# SCH_Mobile-robot.net
KiCad netlist of a schematic drawn in Altium Designer
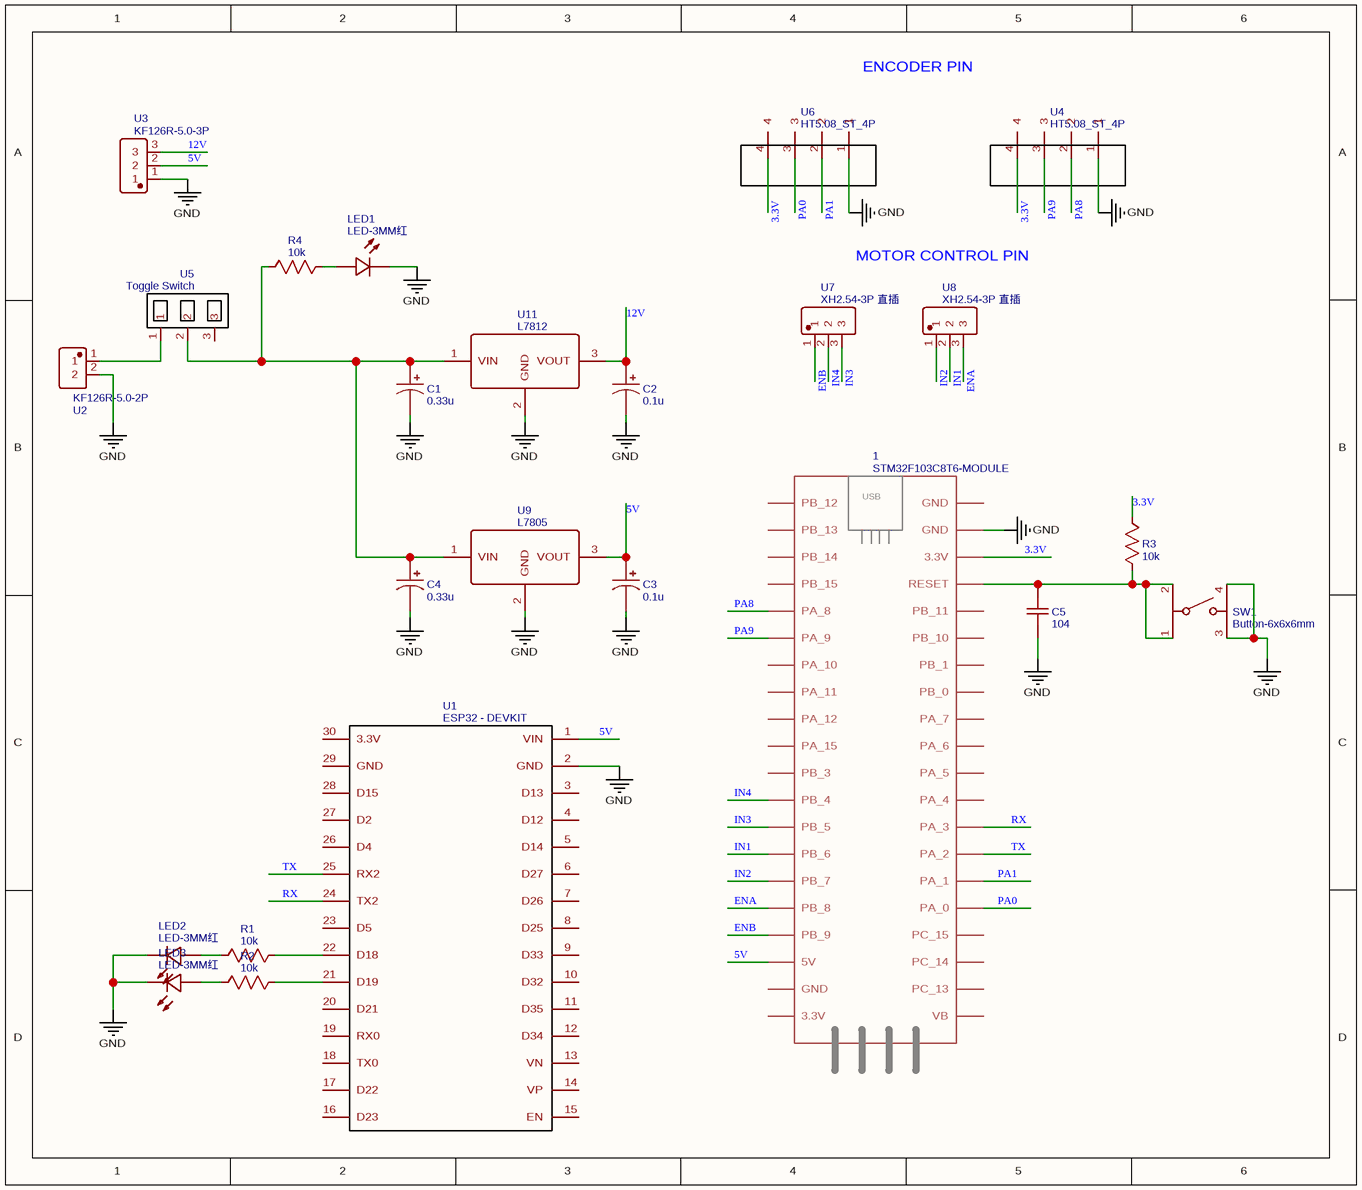
[diagram p0: SCH_Mobile-robot.schdoc]

(export (version "E")
  (design (tool "Eeschema 10.0.6"))
  (components
    (comp (ref "1")
      (value "STM32F103C8T6-MODULE")
      (fields (field (name "CONTRIBUTOR") "minhnhathust2002"))
      (libsource (lib "altium-import") (part "root_3_STM32F103C8T6-MODULE_"))
    )
    (comp (ref "C1")
      (value "0.33u")
      (fields (field (name "CONTRIBUTOR") "LCEDA_Lib"))
      (libsource (lib "altium-import") (part "root_3_0.33u_"))
    )
    (comp (ref "C2")
      (value "0.1u")
      (fields (field (name "CONTRIBUTOR") "LCEDA_Lib"))
      (libsource (lib "altium-import") (part "root_3_0.1u_"))
    )
    (comp (ref "C3")
      (value "0.1u")
      (fields (field (name "CONTRIBUTOR") "LCEDA_Lib"))
      (libsource (lib "altium-import") (part "root_3_0.1u_"))
    )
    (comp (ref "C4")
      (value "0.33u")
      (fields (field (name "CONTRIBUTOR") "LCEDA_Lib"))
      (libsource (lib "altium-import") (part "root_3_0.33u_"))
    )
    (comp (ref "C5")
      (value "104")
      (fields (field (name "CONTRIBUTOR") "LCEDA_Lib"))
      (libsource (lib "altium-import") (part "root_1_104_"))
    )
    (comp (ref "LED1")
      (value "LED-3MM红")
      (fields (field (name "MANUFACTURER PART") "LED-3mm红") (field (name "CONTRIBUTOR") "LCSC"))
      (libsource (lib "altium-import") (part "root_0_LED-3MM红_"))
    )
    (comp (ref "LED2")
      (value "LED-3MM红")
      (fields (field (name "MANUFACTURER PART") "LED-3mm红") (field (name "CONTRIBUTOR") "LCSC"))
      (libsource (lib "altium-import") (part "root_2_LED-3MM红_"))
    )
    (comp (ref "LED3")
      (value "LED-3MM红")
      (fields (field (name "MANUFACTURER PART") "LED-3mm红") (field (name "CONTRIBUTOR") "LCSC"))
      (libsource (lib "altium-import") (part "root_2_LED-3MM红_"))
    )
    (comp (ref "R1")
      (value "10k")
      (fields (field (name "CONTRIBUTOR") "LCEDA_Lib"))
      (libsource (lib "altium-import") (part "root_2_10k_"))
    )
    (comp (ref "R2")
      (value "10k")
      (fields (field (name "CONTRIBUTOR") "LCEDA_Lib"))
      (libsource (lib "altium-import") (part "root_2_10k_"))
    )
    (comp (ref "R3")
      (value "10k")
      (fields (field (name "CONTRIBUTOR") "LCEDA_Lib"))
      (libsource (lib "altium-import") (part "root_3_10k_"))
    )
    (comp (ref "R4")
      (value "10k")
      (fields (field (name "CONTRIBUTOR") "LCEDA_Lib"))
      (libsource (lib "altium-import") (part "root_2_10k_"))
    )
    (comp (ref "SW1")
      (value "Button-6x6x6mm")
      (fields
        (field (name "MANUFACTURER") "BBJ")
        (field (name "MANUFACTURER PART") "Switch,6*6*6Plastic head,260G, 0.25mm,Straight line")
      )
      (libsource (lib "altium-import") (part "root_1_Button-6x6x6mm_"))
    )
    (comp (ref "U1")
      (value "ESP32 - DEVKIT")
      (fields (field (name "CONTRIBUTOR") "minhnhathust2002"))
      (libsource (lib "altium-import") (part "root_0_ESP32 - DEVKIT_"))
    )
    (comp (ref "U2")
      (value "KF126R-5.0-2P")
      (fields (field (name "MANUFACTURER") "KEFA(科发)") (field (name "CONTRIBUTOR") "LCSC"))
      (libsource (lib "altium-import") (part "root_2_KF126R-5.0-2P_"))
    )
    (comp (ref "U3")
      (value "KF126R-5.0-3P")
      (fields (field (name "MANUFACTURER") "KEFA(科发)") (field (name "CONTRIBUTOR") "LCSC"))
      (libsource (lib "altium-import") (part "root_2_KF126R-5.0-3P_"))
    )
    (comp (ref "U4")
      (value "HT5.08_ST_4P")
      (fields (field (name "CONTRIBUTOR") "thomas720"))
      (libsource (lib "altium-import") (part "root_3_HT5.08_ST_4P_"))
    )
    (comp (ref "U5")
      (value "Toggle Switch")
      (fields (field (name "CONTRIBUTOR") "minhnhathust2002"))
      (libsource (lib "altium-import") (part "root_2_Toggle Switch_"))
    )
    (comp (ref "U6")
      (value "HT5.08_ST_4P")
      (fields (field (name "CONTRIBUTOR") "thomas720"))
      (libsource (lib "altium-import") (part "root_3_HT5.08_ST_4P_"))
    )
    (comp (ref "U7")
      (value "XH2.54-3P 直插")
      (fields (field (name "CONTRIBUTOR") "LCSC"))
      (libsource (lib "altium-import") (part "root_1_XH2.54-3P 直插_"))
    )
    (comp (ref "U8")
      (value "XH2.54-3P 直插")
      (fields (field (name "CONTRIBUTOR") "LCSC"))
      (libsource (lib "altium-import") (part "root_1_XH2.54-3P 直插_"))
    )
    (comp (ref "U9")
      (value "L7805")
      (fields
        (field (name "MANUFACTURER") "FeiHong(飞虹)")
        (field (name "MANUFACTURER PART") "KA7812B")
        (field (name "CONTRIBUTOR") "LCSC")
      )
      (libsource (lib "altium-import") (part "root_0_L7805_"))
    )
    (comp (ref "U11")
      (value "L7812")
      (fields
        (field (name "MANUFACTURER") "FeiHong(飞虹)")
        (field (name "MANUFACTURER PART") "KA7812B")
        (field (name "CONTRIBUTOR") "LCSC")
      )
      (libsource (lib "altium-import") (part "root_0_L7812_"))
    )
  )
  (nets
    (net (code "1") (name "/3.3V") (class "Default")
      (node (ref "1") (pin "3.3V_2") (pinfunction "3.3V_3.3V_2") (pintype "passive"))
      (node (ref "R3") (pin "1") (pinfunction "1_1") (pintype "passive"))
      (node (ref "U4") (pin "4") (pinfunction "4_4") (pintype "passive"))
      (node (ref "U6") (pin "4") (pinfunction "4_4") (pintype "passive"))
    )
    (net (code "2") (name "/5V") (class "Default")
      (node (ref "1") (pin "5V") (pinfunction "5V_5V") (pintype "passive"))
      (node (ref "C3") (pin "1") (pinfunction "1_1") (pintype "passive"))
      (node (ref "U1") (pin "1") (pinfunction "VIN_1") (pintype "passive"))
      (node (ref "U3") (pin "2") (pinfunction "2_2") (pintype "passive"))
      (node (ref "U9") (pin "3") (pinfunction "VOUT_3") (pintype "passive"))
    )
    (net (code "3") (name "/12V") (class "Default")
      (node (ref "C2") (pin "1") (pinfunction "1_1") (pintype "passive"))
      (node (ref "U11") (pin "3") (pinfunction "VOUT_3") (pintype "passive"))
      (node (ref "U3") (pin "3") (pinfunction "3_3") (pintype "passive"))
    )
    (net (code "4") (name "/ENA") (class "Default")
      (node (ref "1") (pin "PB_8") (pinfunction "PB_8_PB_8") (pintype "passive"))
      (node (ref "U8") (pin "3") (pinfunction "3_3") (pintype "passive"))
    )
    (net (code "5") (name "/ENB") (class "Default")
      (node (ref "1") (pin "PB_9") (pinfunction "PB_9_PB_9") (pintype "passive"))
      (node (ref "U7") (pin "1") (pinfunction "1_1") (pintype "passive"))
    )
    (net (code "6") (name "/IN1") (class "Default")
      (node (ref "1") (pin "PB_6") (pinfunction "PB_6_PB_6") (pintype "passive"))
      (node (ref "U8") (pin "2") (pinfunction "2_2") (pintype "passive"))
    )
    (net (code "7") (name "/IN2") (class "Default")
      (node (ref "1") (pin "PB_7") (pinfunction "PB_7_PB_7") (pintype "passive"))
      (node (ref "U8") (pin "1") (pinfunction "1_1") (pintype "passive"))
    )
    (net (code "8") (name "/IN3") (class "Default")
      (node (ref "1") (pin "PB_5") (pinfunction "PB_5_PB_5") (pintype "passive"))
      (node (ref "U7") (pin "3") (pinfunction "3_3") (pintype "passive"))
    )
    (net (code "9") (name "/IN4") (class "Default")
      (node (ref "1") (pin "PB_4") (pinfunction "PB_4_PB_4") (pintype "passive"))
      (node (ref "U7") (pin "2") (pinfunction "2_2") (pintype "passive"))
    )
    (net (code "10") (name "/PA0") (class "Default")
      (node (ref "1") (pin "PA_0") (pinfunction "PA_0_PA_0") (pintype "passive"))
      (node (ref "U6") (pin "3") (pinfunction "3_3") (pintype "passive"))
    )
    (net (code "11") (name "/PA1") (class "Default")
      (node (ref "1") (pin "PA_1") (pinfunction "PA_1_PA_1") (pintype "passive"))
      (node (ref "U6") (pin "2") (pinfunction "2_2") (pintype "passive"))
    )
    (net (code "12") (name "/PA8") (class "Default")
      (node (ref "1") (pin "PA_8") (pinfunction "PA_8_PA_8") (pintype "passive"))
      (node (ref "U4") (pin "2") (pinfunction "2_2") (pintype "passive"))
    )
    (net (code "13") (name "/PA9") (class "Default")
      (node (ref "1") (pin "PA_9") (pinfunction "PA_9_PA_9") (pintype "passive"))
      (node (ref "U4") (pin "3") (pinfunction "3_3") (pintype "passive"))
    )
    (net (code "14") (name "/RX") (class "Default")
      (node (ref "1") (pin "PA_3") (pinfunction "PA_3_PA_3") (pintype "passive"))
      (node (ref "U1") (pin "24") (pinfunction "TX2_24") (pintype "passive"))
    )
    (net (code "15") (name "/TX") (class "Default")
      (node (ref "1") (pin "PA_2") (pinfunction "PA_2_PA_2") (pintype "passive"))
      (node (ref "U1") (pin "25") (pinfunction "RX2_25") (pintype "passive"))
    )
    (net (code "16") (name "GND") (class "Default")
      (node (ref "1") (pin "GND_2") (pinfunction "GND_GND_2") (pintype "passive"))
      (node (ref "C1") (pin "2") (pinfunction "2_2") (pintype "passive"))
      (node (ref "C2") (pin "2") (pinfunction "2_2") (pintype "passive"))
      (node (ref "C3") (pin "2") (pinfunction "2_2") (pintype "passive"))
      (node (ref "C4") (pin "2") (pinfunction "2_2") (pintype "passive"))
      (node (ref "C5") (pin "1") (pinfunction "1_1") (pintype "passive"))
      (node (ref "LED1") (pin "2") (pinfunction "2_2") (pintype "passive"))
      (node (ref "LED2") (pin "2") (pinfunction "2_2") (pintype "passive"))
      (node (ref "LED3") (pin "2") (pinfunction "2_2") (pintype "passive"))
      (node (ref "SW1") (pin "3") (pinfunction "3_3") (pintype "passive"))
      (node (ref "SW1") (pin "4") (pinfunction "4_4") (pintype "passive"))
      (node (ref "U1") (pin "2") (pinfunction "GND_2") (pintype "passive"))
      (node (ref "U11") (pin "2") (pinfunction "GND_2") (pintype "passive"))
      (node (ref "U2") (pin "2") (pinfunction "2_2") (pintype "passive"))
      (node (ref "U3") (pin "1") (pinfunction "1_1") (pintype "passive"))
      (node (ref "U4") (pin "1") (pinfunction "1_1") (pintype "passive"))
      (node (ref "U6") (pin "1") (pinfunction "1_1") (pintype "passive"))
      (node (ref "U9") (pin "2") (pinfunction "GND_2") (pintype "passive"))
    )
    (net (code "17") (name "Net-(1-PadRESET)") (class "Default")
      (node (ref "1") (pin "RESET") (pinfunction "RESET_RESET") (pintype "passive"))
      (node (ref "C5") (pin "2") (pinfunction "2_2") (pintype "passive"))
      (node (ref "R3") (pin "2") (pinfunction "2_2") (pintype "passive"))
      (node (ref "SW1") (pin "1") (pinfunction "1_1") (pintype "passive"))
      (node (ref "SW1") (pin "2") (pinfunction "2_2") (pintype "passive"))
    )
    (net (code "18") (name "Net-(LED1-Pad1)") (class "Default")
      (node (ref "LED1") (pin "1") (pinfunction "1_1") (pintype "passive"))
      (node (ref "R4") (pin "1") (pinfunction "1_1") (pintype "passive"))
    )
    (net (code "19") (name "Net-(LED2-Pad1)") (class "Default")
      (node (ref "LED2") (pin "1") (pinfunction "1_1") (pintype "passive"))
      (node (ref "R1") (pin "2") (pinfunction "2_2") (pintype "passive"))
    )
    (net (code "20") (name "Net-(LED3-Pad1)") (class "Default")
      (node (ref "LED3") (pin "1") (pinfunction "1_1") (pintype "passive"))
      (node (ref "R2") (pin "2") (pinfunction "2_2") (pintype "passive"))
    )
    (net (code "21") (name "Net-(U1-D18)") (class "Default")
      (node (ref "R1") (pin "1") (pinfunction "1_1") (pintype "passive"))
      (node (ref "U1") (pin "22") (pinfunction "D18_22") (pintype "passive"))
    )
    (net (code "22") (name "Net-(U1-D19)") (class "Default")
      (node (ref "R2") (pin "1") (pinfunction "1_1") (pintype "passive"))
      (node (ref "U1") (pin "21") (pinfunction "D19_21") (pintype "passive"))
    )
    (net (code "23") (name "Net-(U2-Pad1)") (class "Default")
      (node (ref "U2") (pin "1") (pinfunction "1_1") (pintype "passive"))
      (node (ref "U5") (pin "1") (pinfunction "1_1") (pintype "passive"))
    )
    (net (code "24") (name "Net-(U11-VIN)") (class "Default")
      (node (ref "C1") (pin "1") (pinfunction "1_1") (pintype "passive"))
      (node (ref "C4") (pin "1") (pinfunction "1_1") (pintype "passive"))
      (node (ref "R4") (pin "2") (pinfunction "2_2") (pintype "passive"))
      (node (ref "U11") (pin "1") (pinfunction "VIN_1") (pintype "passive"))
      (node (ref "U5") (pin "2") (pinfunction "2_2") (pintype "passive"))
      (node (ref "U9") (pin "1") (pinfunction "VIN_1") (pintype "passive"))
    )
    (net (code "25") (name "unconnected-(1-3.3V-Pad3.3V_1)") (class "Default")
      (node (ref "1") (pin "3.3V_1") (pinfunction "3.3V_3.3V_1") (pintype "passive"))
    )
    (net (code "26") (name "unconnected-(1-GND-PadGND_1)") (class "Default")
      (node (ref "1") (pin "GND_1") (pinfunction "GND_GND_1") (pintype "passive"))
    )
    (net (code "27") (name "unconnected-(1-GND-PadGND_3)") (class "Default")
      (node (ref "1") (pin "GND_3") (pinfunction "GND_GND_3") (pintype "passive"))
    )
    (net (code "28") (name "unconnected-(1-PadPA_4)") (class "Default")
      (node (ref "1") (pin "PA_4") (pinfunction "PA_4_PA_4") (pintype "passive"))
    )
    (net (code "29") (name "unconnected-(1-PadPA_5)") (class "Default")
      (node (ref "1") (pin "PA_5") (pinfunction "PA_5_PA_5") (pintype "passive"))
    )
    (net (code "30") (name "unconnected-(1-PadPA_6)") (class "Default")
      (node (ref "1") (pin "PA_6") (pinfunction "PA_6_PA_6") (pintype "passive"))
    )
    (net (code "31") (name "unconnected-(1-PadPA_7)") (class "Default")
      (node (ref "1") (pin "PA_7") (pinfunction "PA_7_PA_7") (pintype "passive"))
    )
    (net (code "32") (name "unconnected-(1-PadPA_10)") (class "Default")
      (node (ref "1") (pin "PA_10") (pinfunction "PA_10_PA_10") (pintype "passive"))
    )
    (net (code "33") (name "unconnected-(1-PadPA_11)") (class "Default")
      (node (ref "1") (pin "PA_11") (pinfunction "PA_11_PA_11") (pintype "passive"))
    )
    (net (code "34") (name "unconnected-(1-PadPA_12)") (class "Default")
      (node (ref "1") (pin "PA_12") (pinfunction "PA_12_PA_12") (pintype "passive"))
    )
    (net (code "35") (name "unconnected-(1-PadPA_15)") (class "Default")
      (node (ref "1") (pin "PA_15") (pinfunction "PA_15_PA_15") (pintype "passive"))
    )
    (net (code "36") (name "unconnected-(1-PadPB_0)") (class "Default")
      (node (ref "1") (pin "PB_0") (pinfunction "PB_0_PB_0") (pintype "passive"))
    )
    (net (code "37") (name "unconnected-(1-PadPB_1)") (class "Default")
      (node (ref "1") (pin "PB_1") (pinfunction "PB_1_PB_1") (pintype "passive"))
    )
    (net (code "38") (name "unconnected-(1-PadPB_3)") (class "Default")
      (node (ref "1") (pin "PB_3") (pinfunction "PB_3_PB_3") (pintype "passive"))
    )
    (net (code "39") (name "unconnected-(1-PadPB_10)") (class "Default")
      (node (ref "1") (pin "PB_10") (pinfunction "PB_10_PB_10") (pintype "passive"))
    )
    (net (code "40") (name "unconnected-(1-PadPB_11)") (class "Default")
      (node (ref "1") (pin "PB_11") (pinfunction "PB_11_PB_11") (pintype "passive"))
    )
    (net (code "41") (name "unconnected-(1-PadPB_12)") (class "Default")
      (node (ref "1") (pin "PB_12") (pinfunction "PB_12_PB_12") (pintype "passive"))
    )
    (net (code "42") (name "unconnected-(1-PadPB_13)") (class "Default")
      (node (ref "1") (pin "PB_13") (pinfunction "PB_13_PB_13") (pintype "passive"))
    )
    (net (code "43") (name "unconnected-(1-PadPB_14)") (class "Default")
      (node (ref "1") (pin "PB_14") (pinfunction "PB_14_PB_14") (pintype "passive"))
    )
    (net (code "44") (name "unconnected-(1-PadPB_15)") (class "Default")
      (node (ref "1") (pin "PB_15") (pinfunction "PB_15_PB_15") (pintype "passive"))
    )
    (net (code "45") (name "unconnected-(1-PadPC_13)") (class "Default")
      (node (ref "1") (pin "PC_13") (pinfunction "PC_13_PC_13") (pintype "passive"))
    )
    (net (code "46") (name "unconnected-(1-PadPC_14)") (class "Default")
      (node (ref "1") (pin "PC_14") (pinfunction "PC_14_PC_14") (pintype "passive"))
    )
    (net (code "47") (name "unconnected-(1-PadPC_15)") (class "Default")
      (node (ref "1") (pin "PC_15") (pinfunction "PC_15_PC_15") (pintype "passive"))
    )
    (net (code "48") (name "unconnected-(1-PadVB)") (class "Default")
      (node (ref "1") (pin "VB") (pinfunction "VB_VB") (pintype "passive"))
    )
    (net (code "49") (name "unconnected-(U1-3.3V-Pad30)") (class "Default")
      (node (ref "U1") (pin "30") (pinfunction "3.3V_30") (pintype "passive"))
    )
    (net (code "50") (name "unconnected-(U1-D2-Pad27)") (class "Default")
      (node (ref "U1") (pin "27") (pinfunction "D2_27") (pintype "passive"))
    )
    (net (code "51") (name "unconnected-(U1-D4-Pad26)") (class "Default")
      (node (ref "U1") (pin "26") (pinfunction "D4_26") (pintype "passive"))
    )
    (net (code "52") (name "unconnected-(U1-D5-Pad23)") (class "Default")
      (node (ref "U1") (pin "23") (pinfunction "D5_23") (pintype "passive"))
    )
    (net (code "53") (name "unconnected-(U1-D12-Pad4)") (class "Default")
      (node (ref "U1") (pin "4") (pinfunction "D12_4") (pintype "passive"))
    )
    (net (code "54") (name "unconnected-(U1-D13-Pad3)") (class "Default")
      (node (ref "U1") (pin "3") (pinfunction "D13_3") (pintype "passive"))
    )
    (net (code "55") (name "unconnected-(U1-D14-Pad5)") (class "Default")
      (node (ref "U1") (pin "5") (pinfunction "D14_5") (pintype "passive"))
    )
    (net (code "56") (name "unconnected-(U1-D15-Pad28)") (class "Default")
      (node (ref "U1") (pin "28") (pinfunction "D15_28") (pintype "passive"))
    )
    (net (code "57") (name "unconnected-(U1-D21-Pad20)") (class "Default")
      (node (ref "U1") (pin "20") (pinfunction "D21_20") (pintype "passive"))
    )
    (net (code "58") (name "unconnected-(U1-D22-Pad17)") (class "Default")
      (node (ref "U1") (pin "17") (pinfunction "D22_17") (pintype "passive"))
    )
    (net (code "59") (name "unconnected-(U1-D23-Pad16)") (class "Default")
      (node (ref "U1") (pin "16") (pinfunction "D23_16") (pintype "passive"))
    )
    (net (code "60") (name "unconnected-(U1-D25-Pad8)") (class "Default")
      (node (ref "U1") (pin "8") (pinfunction "D25_8") (pintype "passive"))
    )
    (net (code "61") (name "unconnected-(U1-D26-Pad7)") (class "Default")
      (node (ref "U1") (pin "7") (pinfunction "D26_7") (pintype "passive"))
    )
    (net (code "62") (name "unconnected-(U1-D27-Pad6)") (class "Default")
      (node (ref "U1") (pin "6") (pinfunction "D27_6") (pintype "passive"))
    )
    (net (code "63") (name "unconnected-(U1-D32-Pad10)") (class "Default")
      (node (ref "U1") (pin "10") (pinfunction "D32_10") (pintype "passive"))
    )
    (net (code "64") (name "unconnected-(U1-D33-Pad9)") (class "Default")
      (node (ref "U1") (pin "9") (pinfunction "D33_9") (pintype "passive"))
    )
    (net (code "65") (name "unconnected-(U1-D34-Pad12)") (class "Default")
      (node (ref "U1") (pin "12") (pinfunction "D34_12") (pintype "passive"))
    )
    (net (code "66") (name "unconnected-(U1-D35-Pad11)") (class "Default")
      (node (ref "U1") (pin "11") (pinfunction "D35_11") (pintype "passive"))
    )
    (net (code "67") (name "unconnected-(U1-EN-Pad15)") (class "Default")
      (node (ref "U1") (pin "15") (pinfunction "EN_15") (pintype "passive"))
    )
    (net (code "68") (name "unconnected-(U1-GND-Pad29)") (class "Default")
      (node (ref "U1") (pin "29") (pinfunction "GND_29") (pintype "passive"))
    )
    (net (code "69") (name "unconnected-(U1-RX0-Pad19)") (class "Default")
      (node (ref "U1") (pin "19") (pinfunction "RX0_19") (pintype "passive"))
    )
    (net (code "70") (name "unconnected-(U1-TX0-Pad18)") (class "Default")
      (node (ref "U1") (pin "18") (pinfunction "TX0_18") (pintype "passive"))
    )
    (net (code "71") (name "unconnected-(U1-VN-Pad13)") (class "Default")
      (node (ref "U1") (pin "13") (pinfunction "VN_13") (pintype "passive"))
    )
    (net (code "72") (name "unconnected-(U1-VP-Pad14)") (class "Default")
      (node (ref "U1") (pin "14") (pinfunction "VP_14") (pintype "passive"))
    )
    (net (code "73") (name "unconnected-(U5-Pad3)") (class "Default")
      (node (ref "U5") (pin "3") (pinfunction "3_3") (pintype "passive"))
    )
  )
)
